# Board.net
KiCad netlist of a schematic drawn in Altium Designer
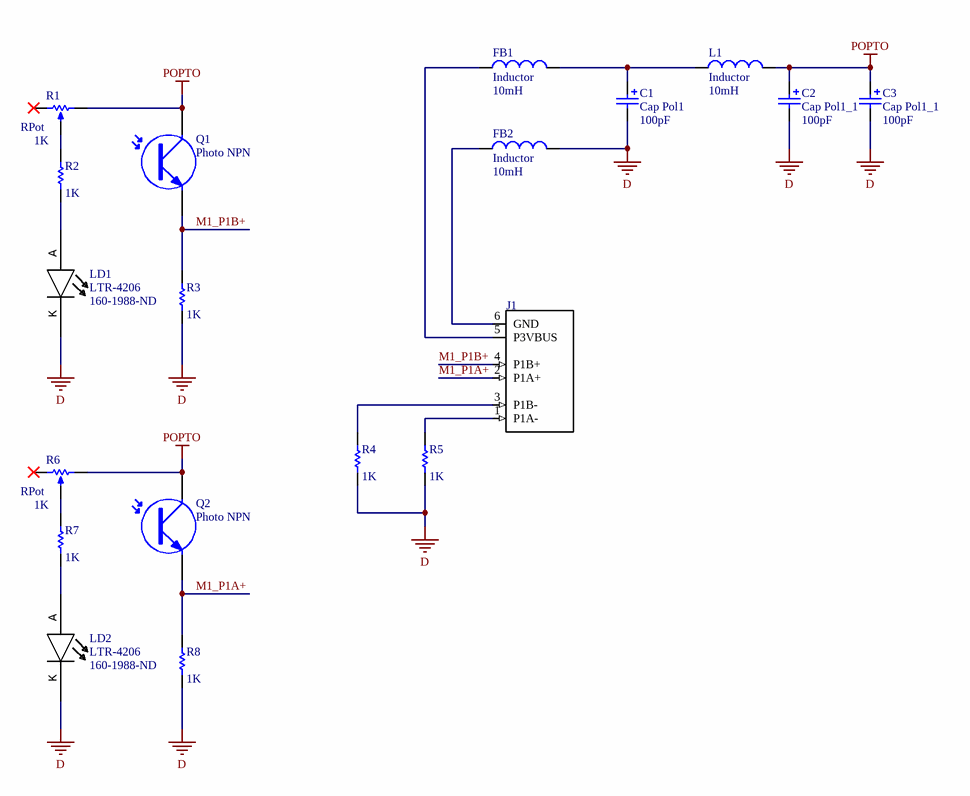
[diagram p0: Board.SchDoc]

(export (version "E")
  (design (tool "Eeschema 10.0.6"))
  (components
    (comp (ref "C1")
      (value "Cap Pol1")
      (footprint "PCAP7343-43_Keme")
      (description "Polarized Capacitor (Radial)")
      (fields (field (name "ALTIUM_VALUE") "100pF") (field (name "PUBLISHER") "Altium Limited"))
      (libsource (lib "RobotSchematics") (part "Cap Pol1"))
    )
    (comp (ref "C2")
      (value "Cap Pol1_1")
      (footprint "805 - CAP Poly")
      (description "Polarized Capacitor 805")
      (fields (field (name "ALTIUM_VALUE") "100pF") (field (name "PUBLISHER") "Altium Limited"))
      (libsource (lib "RobotSchematics") (part "Cap Pol1_1"))
    )
    (comp (ref "C3")
      (value "Cap Pol1_1")
      (footprint "805 - CAP Poly")
      (description "Polarized Capacitor 805")
      (fields (field (name "ALTIUM_VALUE") "100pF") (field (name "PUBLISHER") "Altium Limited"))
      (libsource (lib "RobotSchematics") (part "Cap Pol1_1"))
    )
    (comp (ref "FB1")
      (value "Inductor")
      (footprint "805")
      (fields (field (name "ALTIUM_VALUE") "10mH") (field (name "PUBLISHER") "Altium Limited"))
      (libsource (lib "Miscellaneous Devices") (part "Inductor"))
    )
    (comp (ref "FB2")
      (value "Inductor")
      (footprint "805")
      (fields (field (name "ALTIUM_VALUE") "10mH") (field (name "PUBLISHER") "Altium Limited"))
      (libsource (lib "Miscellaneous Devices") (part "Inductor"))
    )
    (comp (ref "J1")
      (value "640456-6")
      (footprint "TE_640456-6")
      (description "06P MTA100 HDR ASSY F/L SQ STR")
      (fields (field (name "MF") "TE Connectivity"))
      (libsource (lib "RobotSchematics") (part "1x6_6pin_.1_VERTICAL_HEADER"))
    )
    (comp (ref "L1")
      (value "Inductor")
      (footprint "805")
      (fields (field (name "ALTIUM_VALUE") "10mH") (field (name "PUBLISHER") "Altium Limited"))
      (libsource (lib "Miscellaneous Devices") (part "Inductor"))
    )
    (comp (ref "LD1")
      (value "LTR-4206")
      (footprint "LED")
      (fields (field (name "SUPPLIER PART NUMBER 1") "160-1988-ND"))
      (libsource (lib "RobotSchematics") (part "LTR-4206"))
    )
    (comp (ref "LD2")
      (value "LTR-4206")
      (footprint "LED")
      (fields (field (name "SUPPLIER PART NUMBER 1") "160-1988-ND"))
      (libsource (lib "RobotSchematics") (part "LTR-4206"))
    )
    (comp (ref "Q1")
      (value "Photo NPN")
      (footprint "IR - TRANS")
      (description "NPN Phototransistor")
      (fields (field (name "PUBLISHER") "Altium Limited"))
      (libsource (lib "RobotSchematics") (part "Photo NPN"))
    )
    (comp (ref "Q2")
      (value "Photo NPN")
      (footprint "IR - TRANS")
      (description "NPN Phototransistor")
      (fields (field (name "PUBLISHER") "Altium Limited"))
      (libsource (lib "RobotSchematics") (part "Photo NPN"))
    )
    (comp (ref "R1")
      (value "RPot")
      (footprint "ST-4EB")
      (description "Potentiometer")
      (fields (field (name "ALTIUM_VALUE") "1K") (field (name "PUBLISHER") "Altium Limited"))
      (libsource (lib "Miscellaneous Devices") (part "RPot"))
    )
    (comp (ref "R2")
      (value "1K")
      (footprint "805")
      (description "Resistor")
      (fields (field (name "Comment") "Res1") (field (name "PUBLISHER") "Altium Limited"))
      (libsource (lib "Miscellaneous Devices") (part "Res1"))
    )
    (comp (ref "R3")
      (value "1K")
      (footprint "805")
      (description "Resistor")
      (fields (field (name "Comment") "Res1") (field (name "PUBLISHER") "Altium Limited"))
      (libsource (lib "Miscellaneous Devices") (part "Res1"))
    )
    (comp (ref "R4")
      (value "1K")
      (footprint "805")
      (description "Resistor")
      (fields (field (name "Comment") "Res1") (field (name "PUBLISHER") "Altium Limited"))
      (libsource (lib "Miscellaneous Devices") (part "Res1"))
    )
    (comp (ref "R5")
      (value "1K")
      (footprint "805")
      (description "Resistor")
      (fields (field (name "Comment") "Res1") (field (name "PUBLISHER") "Altium Limited"))
      (libsource (lib "Miscellaneous Devices") (part "Res1"))
    )
    (comp (ref "R6")
      (value "RPot")
      (footprint "ST-4EB")
      (description "Potentiometer")
      (fields (field (name "ALTIUM_VALUE") "1K") (field (name "PUBLISHER") "Altium Limited"))
      (libsource (lib "Miscellaneous Devices") (part "RPot"))
    )
    (comp (ref "R7")
      (value "1K")
      (footprint "805")
      (description "Resistor")
      (fields (field (name "Comment") "Res1") (field (name "PUBLISHER") "Altium Limited"))
      (libsource (lib "Miscellaneous Devices") (part "Res1"))
    )
    (comp (ref "R8")
      (value "1K")
      (footprint "805")
      (description "Resistor")
      (fields (field (name "Comment") "Res1") (field (name "PUBLISHER") "Altium Limited"))
      (libsource (lib "Miscellaneous Devices") (part "Res1"))
    )
  )
  (nets
    (net (code "1") (name "/M1_P1A+") (class "Default")
      (node (ref "J1") (pin "2") (pinfunction "P1A+_2") (pintype "input"))
      (node (ref "Q2") (pin "E") (pinfunction "E_E") (pintype "passive"))
      (node (ref "R8") (pin "2") (pinfunction "2_2") (pintype "passive"))
    )
    (net (code "2") (name "/M1_P1B+") (class "Default")
      (node (ref "J1") (pin "4") (pinfunction "P1B+_4") (pintype "input"))
      (node (ref "Q1") (pin "E") (pinfunction "E_E") (pintype "passive"))
      (node (ref "R3") (pin "2") (pinfunction "2_2") (pintype "passive"))
    )
    (net (code "3") (name "D") (class "Default")
      (node (ref "C1") (pin "2") (pinfunction "2_2") (pintype "passive"))
      (node (ref "C2") (pin "2") (pinfunction "2_2") (pintype "passive"))
      (node (ref "C3") (pin "2") (pinfunction "2_2") (pintype "passive"))
      (node (ref "FB2") (pin "2") (pinfunction "2_2") (pintype "passive"))
      (node (ref "LD1") (pin "K") (pinfunction "K_K") (pintype "passive"))
      (node (ref "LD2") (pin "K") (pinfunction "K_K") (pintype "passive"))
      (node (ref "R3") (pin "1") (pinfunction "1_1") (pintype "passive"))
      (node (ref "R4") (pin "1") (pinfunction "1_1") (pintype "passive"))
      (node (ref "R5") (pin "1") (pinfunction "1_1") (pintype "passive"))
      (node (ref "R8") (pin "1") (pinfunction "1_1") (pintype "passive"))
    )
    (net (code "4") (name "Net-(C1-Pad1)") (class "Default")
      (node (ref "C1") (pin "1") (pinfunction "1_1") (pintype "passive"))
      (node (ref "FB1") (pin "2") (pinfunction "2_2") (pintype "passive"))
      (node (ref "L1") (pin "1") (pinfunction "1_1") (pintype "passive"))
    )
    (net (code "5") (name "Net-(J1-GND)") (class "Default")
      (node (ref "FB2") (pin "1") (pinfunction "1_1") (pintype "passive"))
      (node (ref "J1") (pin "6") (pinfunction "GND_6") (pintype "power_in"))
    )
    (net (code "6") (name "Net-(J1-P1A-)") (class "Default")
      (node (ref "J1") (pin "1") (pinfunction "P1A-_1") (pintype "input"))
      (node (ref "R5") (pin "2") (pinfunction "2_2") (pintype "passive"))
    )
    (net (code "7") (name "Net-(J1-P1B-)") (class "Default")
      (node (ref "J1") (pin "3") (pinfunction "P1B-_3") (pintype "input"))
      (node (ref "R4") (pin "2") (pinfunction "2_2") (pintype "passive"))
    )
    (net (code "8") (name "Net-(J1-P3VBUS)") (class "Default")
      (node (ref "FB1") (pin "1") (pinfunction "1_1") (pintype "passive"))
      (node (ref "J1") (pin "5") (pinfunction "P3VBUS_5") (pintype "power_in"))
    )
    (net (code "9") (name "Net-(LD1-PadA)") (class "Default")
      (node (ref "LD1") (pin "A") (pinfunction "A_A") (pintype "passive"))
      (node (ref "R2") (pin "1") (pinfunction "1_1") (pintype "passive"))
    )
    (net (code "10") (name "Net-(LD2-PadA)") (class "Default")
      (node (ref "LD2") (pin "A") (pinfunction "A_A") (pintype "passive"))
      (node (ref "R7") (pin "1") (pinfunction "1_1") (pintype "passive"))
    )
    (net (code "11") (name "Net-(R1-TAP)") (class "Default")
      (node (ref "R1") (pin "3") (pinfunction "TAP_3") (pintype "passive"))
      (node (ref "R2") (pin "2") (pinfunction "2_2") (pintype "passive"))
    )
    (net (code "12") (name "Net-(R6-TAP)") (class "Default")
      (node (ref "R6") (pin "3") (pinfunction "TAP_3") (pintype "passive"))
      (node (ref "R7") (pin "2") (pinfunction "2_2") (pintype "passive"))
    )
    (net (code "13") (name "POPTO") (class "Default")
      (node (ref "C2") (pin "1") (pinfunction "1_1") (pintype "passive"))
      (node (ref "C3") (pin "1") (pinfunction "1_1") (pintype "passive"))
      (node (ref "L1") (pin "2") (pinfunction "2_2") (pintype "passive"))
      (node (ref "Q1") (pin "C") (pinfunction "C_C") (pintype "passive"))
      (node (ref "Q2") (pin "C") (pinfunction "C_C") (pintype "passive"))
      (node (ref "R1") (pin "2") (pinfunction "BOT_2") (pintype "passive"))
      (node (ref "R6") (pin "2") (pinfunction "BOT_2") (pintype "passive"))
    )
    (net (code "14") (name "unconnected-(R1-TOP-Pad1)") (class "Default")
      (node (ref "R1") (pin "1") (pinfunction "TOP_1") (pintype "passive+no_connect"))
    )
    (net (code "15") (name "unconnected-(R6-TOP-Pad1)") (class "Default")
      (node (ref "R6") (pin "1") (pinfunction "TOP_1") (pintype "passive+no_connect"))
    )
  )
)
